# djb_v2_jig.net
KiCad netlist of a schematic drawn in Altium Designer
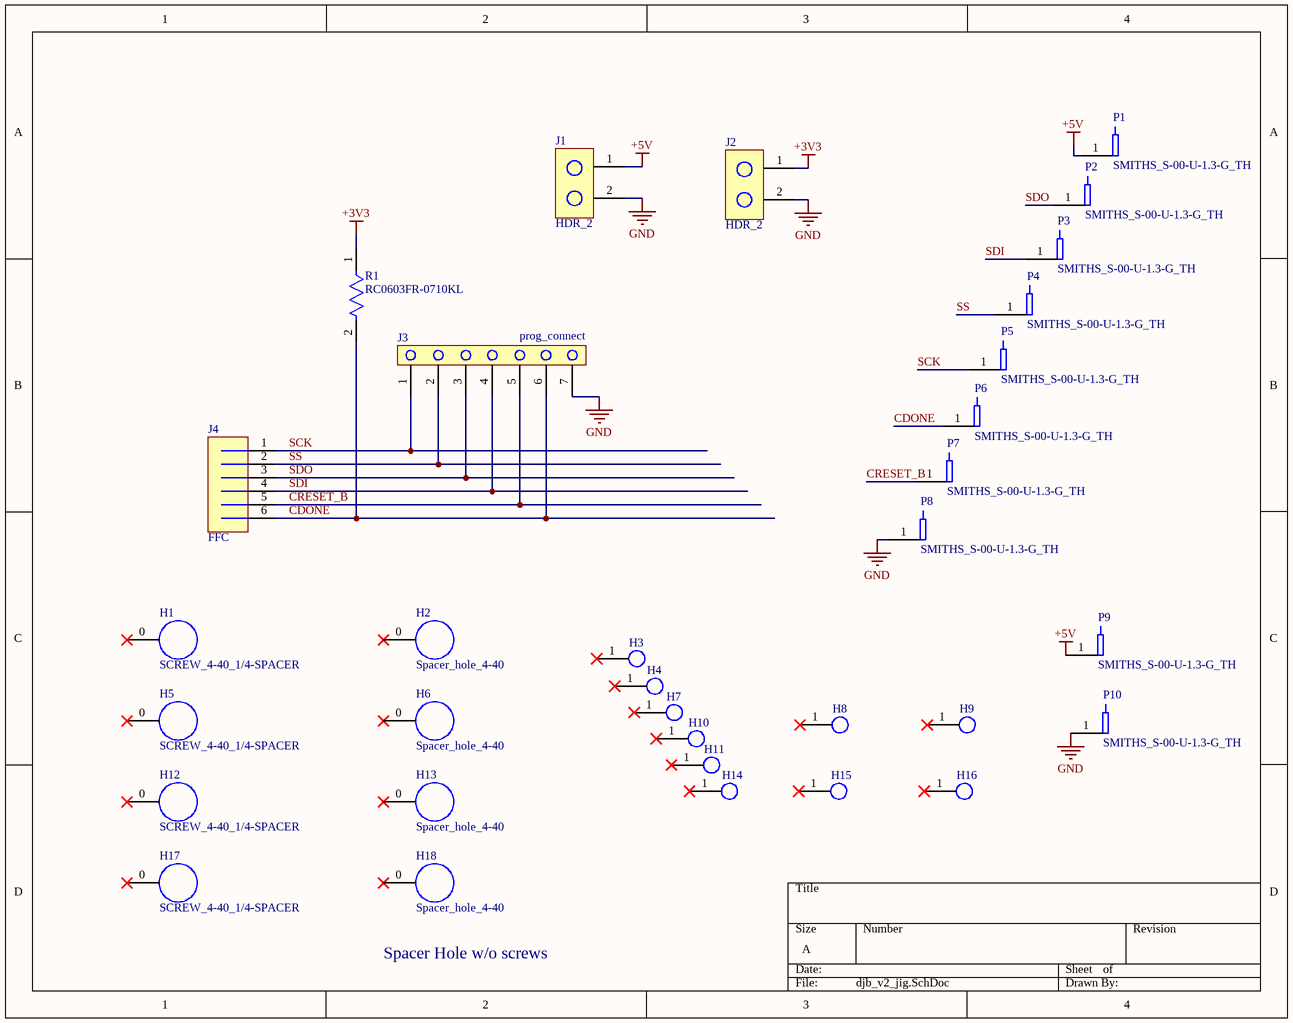
[diagram p0: djb_v2_jig.SchDoc]

(export (version "E")
  (design (tool "Eeschema 10.0.6"))
  (components
    (comp (ref "H1")
      (value "SCREW_4-40_1/4-SPACER")
      (footprint "SCREW_4-40_1/4-SPACER")
      (description "Hole for 4-40 screw with 1/4\" spacer")
      (libsource (lib "OSP_DJB_JIG") (part "SCREW_4-40_1/4-SPACER"))
    )
    (comp (ref "H2")
      (value "Spacer_hole_4-40")
      (footprint "SPACER_HOLE_4-40")
      (description "Spacer hole w/o screw")
      (libsource (lib "OSP_DJB_JIG") (part "Spacer_hole_4-40"))
    )
    (comp (ref "H3")
      (value "SMITHS_S-00-U-1.3_hole")
      (footprint "SMITHS_S-00-U-1.3_hole")
      (description "Smiths Interconnect / IDI S-00-U-1.3-G Pogo Pin 0.99mm Centers 16.7mm Long 2.8mm Travel, Mid Mount")
      (libsource (lib "OSP_DJB_JIG") (part "SMITHS_S-00-U-1.3_hole"))
    )
    (comp (ref "H4")
      (value "SMITHS_S-00-U-1.3_hole")
      (footprint "SMITHS_S-00-U-1.3_hole")
      (description "Smiths Interconnect / IDI S-00-U-1.3-G Pogo Pin 0.99mm Centers 16.7mm Long 2.8mm Travel, Mid Mount")
      (libsource (lib "OSP_DJB_JIG") (part "SMITHS_S-00-U-1.3_hole"))
    )
    (comp (ref "H5")
      (value "SCREW_4-40_1/4-SPACER")
      (footprint "SCREW_4-40_1/4-SPACER")
      (description "Hole for 4-40 screw with 1/4\" spacer")
      (libsource (lib "OSP_DJB_JIG") (part "SCREW_4-40_1/4-SPACER"))
    )
    (comp (ref "H6")
      (value "Spacer_hole_4-40")
      (footprint "SPACER_HOLE_4-40")
      (description "Spacer hole w/o screw")
      (libsource (lib "OSP_DJB_JIG") (part "Spacer_hole_4-40"))
    )
    (comp (ref "H7")
      (value "SMITHS_S-00-U-1.3_hole")
      (footprint "SMITHS_S-00-U-1.3_hole")
      (description "Smiths Interconnect / IDI S-00-U-1.3-G Pogo Pin 0.99mm Centers 16.7mm Long 2.8mm Travel, Mid Mount")
      (libsource (lib "OSP_DJB_JIG") (part "SMITHS_S-00-U-1.3_hole"))
    )
    (comp (ref "H8")
      (value "SMITHS_S-00-U-1.3_hole")
      (footprint "SMITHS_S-00-U-1.3_hole")
      (description "Smiths Interconnect / IDI S-00-U-1.3-G Pogo Pin 0.99mm Centers 16.7mm Long 2.8mm Travel, Mid Mount")
      (libsource (lib "OSP_DJB_JIG") (part "SMITHS_S-00-U-1.3_hole"))
    )
    (comp (ref "H9")
      (value "SMITHS_S-00-U-1.3_hole")
      (footprint "SMITHS_S-00-U-1.3_hole")
      (description "Smiths Interconnect / IDI S-00-U-1.3-G Pogo Pin 0.99mm Centers 16.7mm Long 2.8mm Travel, Mid Mount")
      (libsource (lib "OSP_DJB_JIG") (part "SMITHS_S-00-U-1.3_hole"))
    )
    (comp (ref "H10")
      (value "SMITHS_S-00-U-1.3_hole")
      (footprint "SMITHS_S-00-U-1.3_hole")
      (description "Smiths Interconnect / IDI S-00-U-1.3-G Pogo Pin 0.99mm Centers 16.7mm Long 2.8mm Travel, Mid Mount")
      (libsource (lib "OSP_DJB_JIG") (part "SMITHS_S-00-U-1.3_hole"))
    )
    (comp (ref "H11")
      (value "SMITHS_S-00-U-1.3_hole")
      (footprint "SMITHS_S-00-U-1.3_hole")
      (description "Smiths Interconnect / IDI S-00-U-1.3-G Pogo Pin 0.99mm Centers 16.7mm Long 2.8mm Travel, Mid Mount")
      (libsource (lib "OSP_DJB_JIG") (part "SMITHS_S-00-U-1.3_hole"))
    )
    (comp (ref "H12")
      (value "SCREW_4-40_1/4-SPACER")
      (footprint "SCREW_4-40_1/4-SPACER")
      (description "Hole for 4-40 screw with 1/4\" spacer")
      (libsource (lib "OSP_DJB_JIG") (part "SCREW_4-40_1/4-SPACER"))
    )
    (comp (ref "H13")
      (value "Spacer_hole_4-40")
      (footprint "SPACER_HOLE_4-40")
      (description "Spacer hole w/o screw")
      (libsource (lib "OSP_DJB_JIG") (part "Spacer_hole_4-40"))
    )
    (comp (ref "H14")
      (value "SMITHS_S-00-U-1.3_hole")
      (footprint "SMITHS_S-00-U-1.3_hole")
      (description "Smiths Interconnect / IDI S-00-U-1.3-G Pogo Pin 0.99mm Centers 16.7mm Long 2.8mm Travel, Mid Mount")
      (libsource (lib "OSP_DJB_JIG") (part "SMITHS_S-00-U-1.3_hole"))
    )
    (comp (ref "H15")
      (value "SMITHS_S-00-U-1.3_hole")
      (footprint "SMITHS_S-00-U-1.3_hole")
      (description "Smiths Interconnect / IDI S-00-U-1.3-G Pogo Pin 0.99mm Centers 16.7mm Long 2.8mm Travel, Mid Mount")
      (libsource (lib "OSP_DJB_JIG") (part "SMITHS_S-00-U-1.3_hole"))
    )
    (comp (ref "H16")
      (value "SMITHS_S-00-U-1.3_hole")
      (footprint "SMITHS_S-00-U-1.3_hole")
      (description "Smiths Interconnect / IDI S-00-U-1.3-G Pogo Pin 0.99mm Centers 16.7mm Long 2.8mm Travel, Mid Mount")
      (libsource (lib "OSP_DJB_JIG") (part "SMITHS_S-00-U-1.3_hole"))
    )
    (comp (ref "H17")
      (value "SCREW_4-40_1/4-SPACER")
      (footprint "SCREW_4-40_1/4-SPACER")
      (description "Hole for 4-40 screw with 1/4\" spacer")
      (libsource (lib "OSP_DJB_JIG") (part "SCREW_4-40_1/4-SPACER"))
    )
    (comp (ref "H18")
      (value "Spacer_hole_4-40")
      (footprint "SPACER_HOLE_4-40")
      (description "Spacer hole w/o screw")
      (libsource (lib "OSP_DJB_JIG") (part "Spacer_hole_4-40"))
    )
    (comp (ref "J1")
      (value "HDR_2")
      (footprint "2-POS_HEADER")
      (description "2-pin 0.1\" header")
      (libsource (lib "OSP_DJB_JIG") (part "HDR_2"))
    )
    (comp (ref "J2")
      (value "HDR_2")
      (footprint "2-POS_HEADER")
      (description "2-pin 0.1\" header")
      (libsource (lib "OSP_DJB_JIG") (part "HDR_2"))
    )
    (comp (ref "J3")
      (value "prog_connect")
      (footprint "7-pos_header")
      (description "7-pos male pin header, 2.54mm pitch")
      (libsource (lib "OSP_DJB_JIG") (part "prog_connect"))
    )
    (comp (ref "J4")
      (value "FFC")
      (footprint "AMPHENOL_HFW6R-1STE1LF")
      (description "Amphenol HFW6R-1STE1LF 6-pin flat flexible cable connector")
      (libsource (lib "OSP_DJB_JIG") (part "AMPHENOL_HFW6R-1STE1LF"))
    )
    (comp (ref "P1")
      (value "SMITHS_S-00-U-1.3-G_TH")
      (footprint "SMITHS_S-00-U-1.3-G_TH")
      (libsource (lib "OSP_DJB_JIG") (part "SMITHS_S-00-U-1.3-G_TH"))
    )
    (comp (ref "P2")
      (value "SMITHS_S-00-U-1.3-G_TH")
      (footprint "SMITHS_S-00-U-1.3-G_TH")
      (libsource (lib "OSP_DJB_JIG") (part "SMITHS_S-00-U-1.3-G_TH"))
    )
    (comp (ref "P3")
      (value "SMITHS_S-00-U-1.3-G_TH")
      (footprint "SMITHS_S-00-U-1.3-G_TH")
      (libsource (lib "OSP_DJB_JIG") (part "SMITHS_S-00-U-1.3-G_TH"))
    )
    (comp (ref "P4")
      (value "SMITHS_S-00-U-1.3-G_TH")
      (footprint "SMITHS_S-00-U-1.3-G_TH")
      (libsource (lib "OSP_DJB_JIG") (part "SMITHS_S-00-U-1.3-G_TH"))
    )
    (comp (ref "P5")
      (value "SMITHS_S-00-U-1.3-G_TH")
      (footprint "SMITHS_S-00-U-1.3-G_TH")
      (libsource (lib "OSP_DJB_JIG") (part "SMITHS_S-00-U-1.3-G_TH"))
    )
    (comp (ref "P6")
      (value "SMITHS_S-00-U-1.3-G_TH")
      (footprint "SMITHS_S-00-U-1.3-G_TH")
      (libsource (lib "OSP_DJB_JIG") (part "SMITHS_S-00-U-1.3-G_TH"))
    )
    (comp (ref "P7")
      (value "SMITHS_S-00-U-1.3-G_TH")
      (footprint "SMITHS_S-00-U-1.3-G_TH")
      (libsource (lib "OSP_DJB_JIG") (part "SMITHS_S-00-U-1.3-G_TH"))
    )
    (comp (ref "P8")
      (value "SMITHS_S-00-U-1.3-G_TH")
      (footprint "SMITHS_S-00-U-1.3-G_TH")
      (libsource (lib "OSP_DJB_JIG") (part "SMITHS_S-00-U-1.3-G_TH"))
    )
    (comp (ref "P9")
      (value "SMITHS_S-00-U-1.3-G_TH")
      (footprint "SMITHS_S-00-U-1.3-G_TH")
      (libsource (lib "OSP_DJB_JIG") (part "SMITHS_S-00-U-1.3-G_TH"))
    )
    (comp (ref "P10")
      (value "SMITHS_S-00-U-1.3-G_TH")
      (footprint "SMITHS_S-00-U-1.3-G_TH")
      (libsource (lib "OSP_DJB_JIG") (part "SMITHS_S-00-U-1.3-G_TH"))
    )
    (comp (ref "R1")
      (value "RC0603FR-0710KL")
      (footprint "FP-RC0603-0_55-IPC_C")
      (description "RES 10K OHM 1% 1/10W 0603")
      (fields (field (name "TOLERANCE") "1%"))
      (libsource (lib "Altium Content Vault") (part "1029c3af85768c4190bb7ad29bc67b5"))
    )
  )
  (nets
    (net (code "1") (name "+3V3") (class "Default")
      (node (ref "J2") (pin "1") (pinfunction "1_1") (pintype "passive"))
      (node (ref "R1") (pin "1") (pinfunction "1_1") (pintype "passive"))
    )
    (net (code "2") (name "+5V") (class "Default")
      (node (ref "J1") (pin "1") (pinfunction "1_1") (pintype "passive"))
      (node (ref "P1") (pin "1") (pinfunction "1_1") (pintype "passive"))
      (node (ref "P9") (pin "1") (pinfunction "1_1") (pintype "passive"))
    )
    (net (code "3") (name "/CDONE") (class "Default")
      (node (ref "J3") (pin "6") (pinfunction "21_6") (pintype "passive"))
      (node (ref "J4") (pin "6") (pintype "passive"))
      (node (ref "P6") (pin "1") (pinfunction "1_1") (pintype "passive"))
      (node (ref "R1") (pin "2") (pinfunction "2_2") (pintype "passive"))
    )
    (net (code "4") (name "/CRESET_B") (class "Default")
      (node (ref "J3") (pin "5") (pinfunction "20_5") (pintype "passive"))
      (node (ref "J4") (pin "5") (pintype "passive"))
      (node (ref "P7") (pin "1") (pinfunction "1_1") (pintype "passive"))
    )
    (net (code "5") (name "/SCK") (class "Default")
      (node (ref "J3") (pin "1") (pinfunction "16_1") (pintype "passive"))
      (node (ref "J4") (pin "1") (pintype "passive"))
      (node (ref "P5") (pin "1") (pinfunction "1_1") (pintype "passive"))
    )
    (net (code "6") (name "/SDI") (class "Default")
      (node (ref "J3") (pin "4") (pinfunction "19_4") (pintype "passive"))
      (node (ref "J4") (pin "4") (pintype "passive"))
      (node (ref "P3") (pin "1") (pinfunction "1_1") (pintype "passive"))
    )
    (net (code "7") (name "/SDO") (class "Default")
      (node (ref "J3") (pin "3") (pinfunction "18_3") (pintype "passive"))
      (node (ref "J4") (pin "3") (pintype "passive"))
      (node (ref "P2") (pin "1") (pinfunction "1_1") (pintype "passive"))
    )
    (net (code "8") (name "/SS") (class "Default")
      (node (ref "J3") (pin "2") (pinfunction "17_2") (pintype "passive"))
      (node (ref "J4") (pin "2") (pintype "passive"))
      (node (ref "P4") (pin "1") (pinfunction "1_1") (pintype "passive"))
    )
    (net (code "9") (name "GND") (class "Default")
      (node (ref "J1") (pin "2") (pinfunction "2_2") (pintype "passive"))
      (node (ref "J2") (pin "2") (pinfunction "2_2") (pintype "passive"))
      (node (ref "J3") (pin "7") (pinfunction "7_7") (pintype "passive"))
      (node (ref "P10") (pin "1") (pinfunction "1_1") (pintype "passive"))
      (node (ref "P8") (pin "1") (pinfunction "1_1") (pintype "passive"))
    )
    (net (code "10") (name "unconnected-(H1-Pad0)") (class "Default")
      (node (ref "H1") (pin "0") (pinfunction "0_0") (pintype "passive+no_connect"))
    )
    (net (code "11") (name "unconnected-(H2-Pad0)") (class "Default")
      (node (ref "H2") (pin "0") (pinfunction "0_0") (pintype "passive+no_connect"))
    )
    (net (code "12") (name "unconnected-(H3-Pad1)") (class "Default")
      (node (ref "H3") (pin "1") (pinfunction "1_1") (pintype "passive+no_connect"))
    )
    (net (code "13") (name "unconnected-(H4-Pad1)") (class "Default")
      (node (ref "H4") (pin "1") (pinfunction "1_1") (pintype "passive+no_connect"))
    )
    (net (code "14") (name "unconnected-(H5-Pad0)") (class "Default")
      (node (ref "H5") (pin "0") (pinfunction "0_0") (pintype "passive+no_connect"))
    )
    (net (code "15") (name "unconnected-(H6-Pad0)") (class "Default")
      (node (ref "H6") (pin "0") (pinfunction "0_0") (pintype "passive+no_connect"))
    )
    (net (code "16") (name "unconnected-(H7-Pad1)") (class "Default")
      (node (ref "H7") (pin "1") (pinfunction "1_1") (pintype "passive+no_connect"))
    )
    (net (code "17") (name "unconnected-(H8-Pad1)") (class "Default")
      (node (ref "H8") (pin "1") (pinfunction "1_1") (pintype "passive+no_connect"))
    )
    (net (code "18") (name "unconnected-(H9-Pad1)") (class "Default")
      (node (ref "H9") (pin "1") (pinfunction "1_1") (pintype "passive+no_connect"))
    )
    (net (code "19") (name "unconnected-(H10-Pad1)") (class "Default")
      (node (ref "H10") (pin "1") (pinfunction "1_1") (pintype "passive+no_connect"))
    )
    (net (code "20") (name "unconnected-(H11-Pad1)") (class "Default")
      (node (ref "H11") (pin "1") (pinfunction "1_1") (pintype "passive+no_connect"))
    )
    (net (code "21") (name "unconnected-(H12-Pad0)") (class "Default")
      (node (ref "H12") (pin "0") (pinfunction "0_0") (pintype "passive+no_connect"))
    )
    (net (code "22") (name "unconnected-(H13-Pad0)") (class "Default")
      (node (ref "H13") (pin "0") (pinfunction "0_0") (pintype "passive+no_connect"))
    )
    (net (code "23") (name "unconnected-(H14-Pad1)") (class "Default")
      (node (ref "H14") (pin "1") (pinfunction "1_1") (pintype "passive+no_connect"))
    )
    (net (code "24") (name "unconnected-(H15-Pad1)") (class "Default")
      (node (ref "H15") (pin "1") (pinfunction "1_1") (pintype "passive+no_connect"))
    )
    (net (code "25") (name "unconnected-(H16-Pad1)") (class "Default")
      (node (ref "H16") (pin "1") (pinfunction "1_1") (pintype "passive+no_connect"))
    )
    (net (code "26") (name "unconnected-(H17-Pad0)") (class "Default")
      (node (ref "H17") (pin "0") (pinfunction "0_0") (pintype "passive+no_connect"))
    )
    (net (code "27") (name "unconnected-(H18-Pad0)") (class "Default")
      (node (ref "H18") (pin "0") (pinfunction "0_0") (pintype "passive+no_connect"))
    )
  )
)
